# 3_3V_Supply.net
KiCad netlist of a schematic drawn in Altium Designer
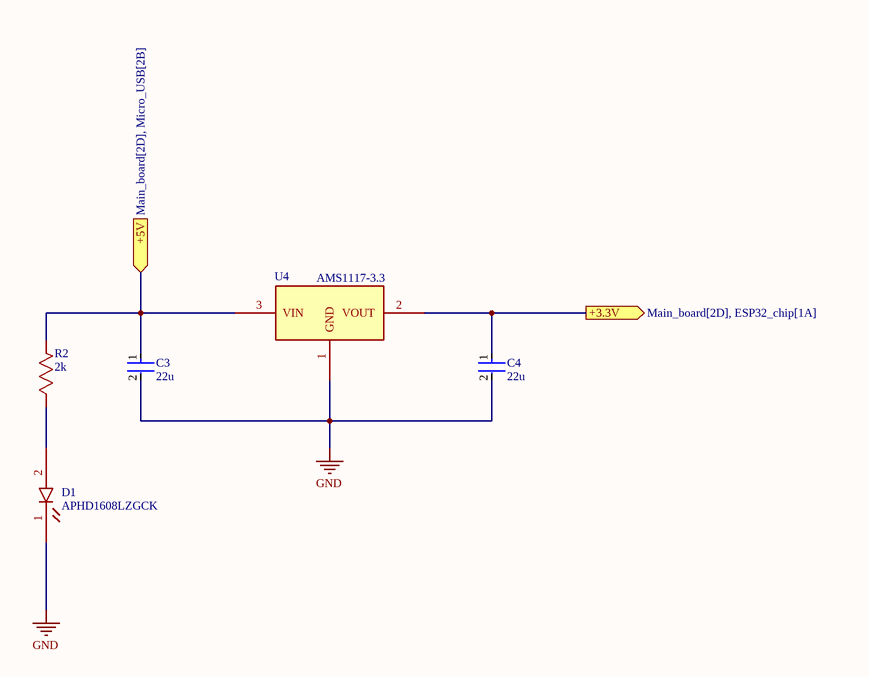
[diagram p0: 3.3V_Supply.SchDoc]

(export (version "E")
  (design (tool "Eeschema 10.0.6"))
  (components
    (comp (ref "C3")
      (value "22u")
      (footprint "FP-GRM21B-0_15-IPC_A")
      (description "0805 22 uF 10 V ±20% Tolerance X5R SMT Multilayer Ceramic Capacitor")
      (fields
        (field (name "MANUFACTURER") "Murata")
        (field (name "MANUFACTURER PART NUMBER") "GRM21BR61A226ME51L")
      )
      (libsource (lib "ESP32") (part "GRM21BR61A226ME51L"))
    )
    (comp (ref "C4")
      (value "22u")
      (footprint "FP-GRM21B-0_15-IPC_A")
      (description "0805 22 uF 10 V ±20% Tolerance X5R SMT Multilayer Ceramic Capacitor")
      (fields
        (field (name "MANUFACTURER") "Murata")
        (field (name "MANUFACTURER PART NUMBER") "GRM21BR61A226ME51L")
      )
      (libsource (lib "ESP32") (part "GRM21BR61A226ME51L"))
    )
    (comp (ref "D1")
      (value "APHD1608LZGCK")
      (footprint "FP-APHD1608LZGCK-MFG")
      (description "Standard LEDs; SMD 0608 Compact Dome Lens LED; 1.6x0.8 mm; Green; (Cut Reel)")
      (fields (field (name "MANUFACTURER") "Kingbright"))
      (libsource (lib "ESP32") (part "APHD1608LZGCK"))
    )
    (comp (ref "R2")
      (value "2k")
      (footprint "FP-CRGCQ0805-IPC_A")
      (description "Res Thick Film 0805 2K Ohm 1% 0.125W(1/8W) ±100ppm/C Pad SMD T/R")
      (fields
        (field (name "MANUFACTURER") "TE Connectivity")
        (field (name "MANUFACTURER PART NUMBER") "1623173-1")
      )
      (libsource (lib "ESP32") (part "1623173-1"))
    )
    (comp (ref "U4")
      (value "AMS1117-3.3")
      (footprint "AMS1117")
      (libsource (lib "ESP32") (part "AMS1117-3.3"))
    )
  )
  (nets
    (net (code "1") (name "/+3.3V") (class "Default")
      (node (ref "C4") (pin "1") (pinfunction "1_1") (pintype "passive"))
      (node (ref "U4") (pin "2") (pinfunction "VOUT_2") (pintype "passive"))
    )
    (net (code "2") (name "/+5V") (class "Default")
      (node (ref "C3") (pin "1") (pinfunction "1_1") (pintype "passive"))
      (node (ref "R2") (pin "2") (pinfunction "2_2") (pintype "passive"))
      (node (ref "U4") (pin "3") (pinfunction "VIN_3") (pintype "passive"))
    )
    (net (code "3") (name "GND") (class "Default")
      (node (ref "C3") (pin "2") (pinfunction "2_2") (pintype "passive"))
      (node (ref "C4") (pin "2") (pinfunction "2_2") (pintype "passive"))
      (node (ref "D1") (pin "1") (pinfunction "1_1") (pintype "passive"))
      (node (ref "U4") (pin "1") (pinfunction "GND_1") (pintype "passive"))
    )
    (net (code "4") (name "Net-(D1-Pad2)") (class "Default")
      (node (ref "D1") (pin "2") (pinfunction "2_2") (pintype "passive"))
      (node (ref "R2") (pin "1") (pinfunction "1_1") (pintype "passive"))
    )
  )
)
